# Fuente.net
KiCad netlist of a schematic drawn in Altium Designer
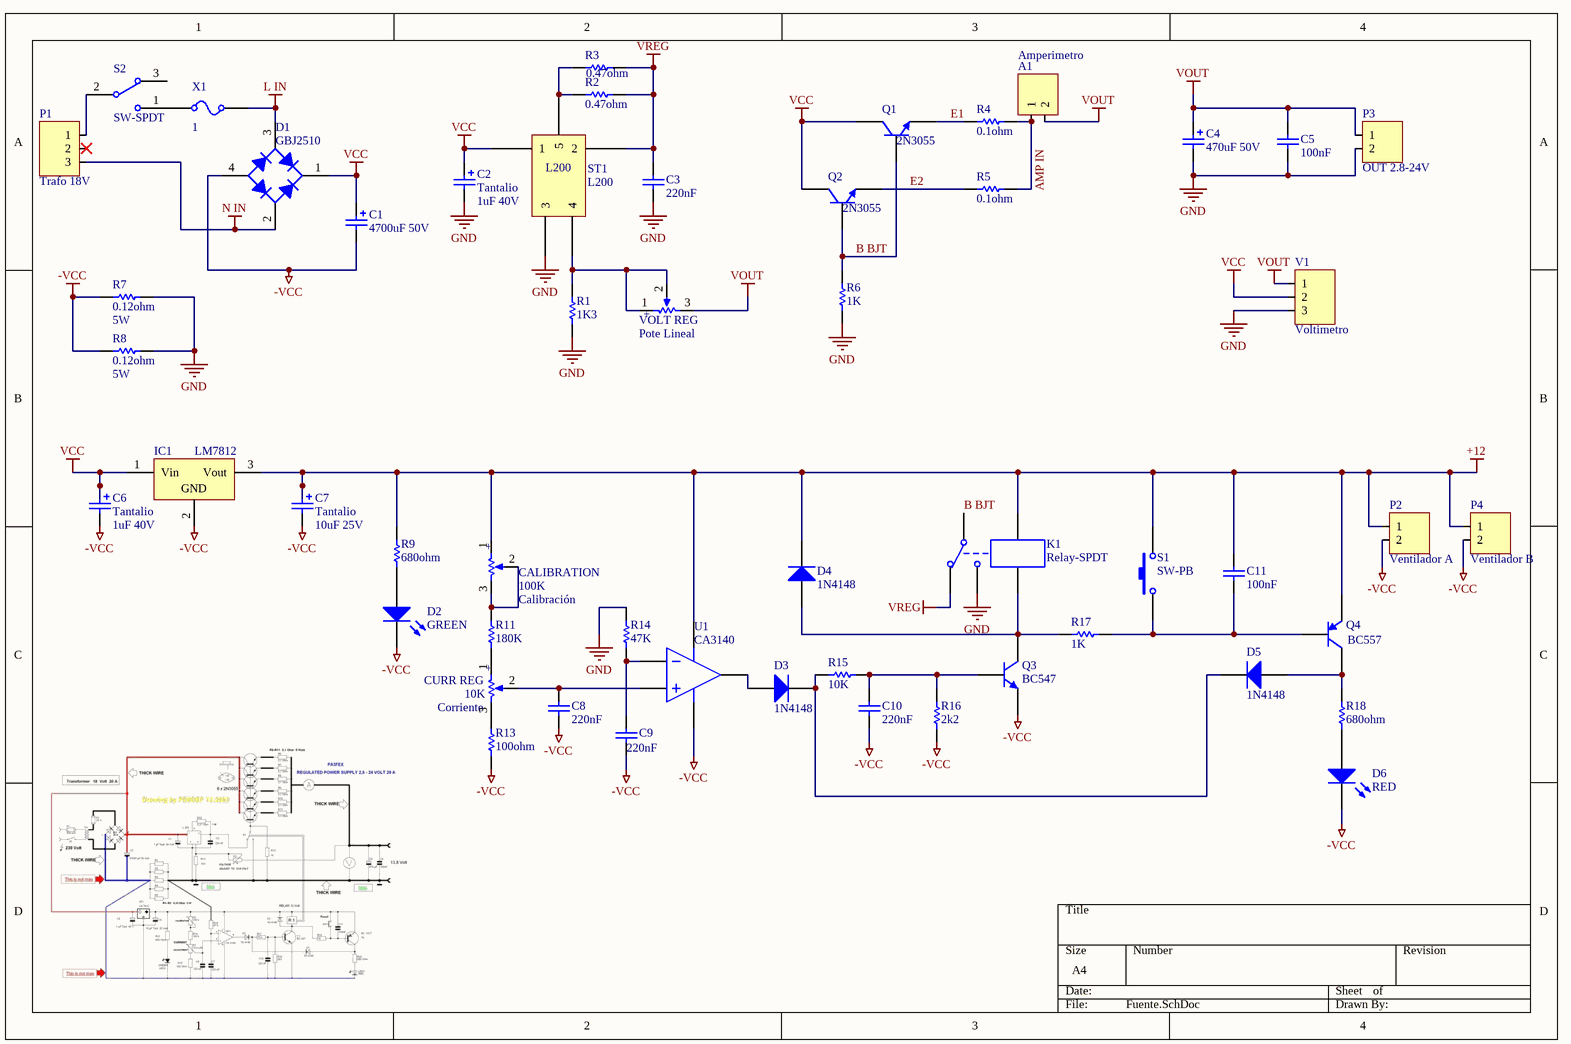
[diagram p0: Fuente.SchDoc]

(export (version "E")
  (design (tool "Eeschema 10.0.6"))
  (components
    (comp (ref "A1")
      (value "Amperimetro")
      (footprint "BORNERA 2")
      (description "Header, 2-Pin")
      (fields (field (name "PUBLISHER") "Altium Limited"))
      (libsource (lib "") (part "Bornera_1"))
    )
    (comp (ref "C1")
      (value "4700uF 50V")
      (footprint "CAP 20MM")
      (description "Polarized Capacitor (Radial)")
      (fields (field (name "PUBLISHER") "Altium Limited"))
      (libsource (lib "SchLibPutallaz") (part "Cap Pol1"))
    )
    (comp (ref "C2")
      (value "Tantalio")
      (footprint "Cap Tantalio")
      (description "Polarized Capacitor (Radial)")
      (fields (field (name "ALTIUM_VALUE") "1uF 40V") (field (name "PUBLISHER") "Altium Limited"))
      (libsource (lib "SchLibPutallaz") (part "Cap Pol1"))
    )
    (comp (ref "C3")
      (value "220nF")
      (footprint "1206 res")
      (description "Capacitor")
      (fields (field (name "PUBLISHER") "Altium Limited"))
      (libsource (lib "SchLibPutallaz") (part "Cap"))
    )
    (comp (ref "C4")
      (value "470uF 50V")
      (footprint "CAP 10mm")
      (description "Polarized Capacitor (Radial)")
      (fields (field (name "PUBLISHER") "Altium Limited"))
      (libsource (lib "SchLibPutallaz") (part "Cap Pol1"))
    )
    (comp (ref "C5")
      (value "100nF")
      (footprint "0805 res")
      (description "Capacitor")
      (fields (field (name "PUBLISHER") "Altium Limited"))
      (libsource (lib "SchLibPutallaz") (part "Cap"))
    )
    (comp (ref "C6")
      (value "Tantalio")
      (footprint "Cap Tantalio")
      (description "Polarized Capacitor (Radial)")
      (fields (field (name "ALTIUM_VALUE") "1uF 40V") (field (name "PUBLISHER") "Altium Limited"))
      (libsource (lib "SchLibPutallaz") (part "Cap Pol1"))
    )
    (comp (ref "C7")
      (value "Tantalio")
      (footprint "Cap Tantalio")
      (description "Polarized Capacitor (Radial)")
      (fields (field (name "ALTIUM_VALUE") "10uF 25V") (field (name "PUBLISHER") "Altium Limited"))
      (libsource (lib "SchLibPutallaz") (part "Cap Pol1"))
    )
    (comp (ref "C8")
      (value "220nF")
      (footprint "1206 res")
      (description "Capacitor")
      (fields (field (name "PUBLISHER") "Altium Limited"))
      (libsource (lib "SchLibPutallaz") (part "Cap"))
    )
    (comp (ref "C9")
      (value "220nF")
      (footprint "1206 res")
      (description "Capacitor")
      (fields (field (name "PUBLISHER") "Altium Limited"))
      (libsource (lib "SchLibPutallaz") (part "Cap"))
    )
    (comp (ref "C10")
      (value "220nF")
      (footprint "1206 res")
      (description "Capacitor")
      (fields (field (name "PUBLISHER") "Altium Limited"))
      (libsource (lib "SchLibPutallaz") (part "Cap"))
    )
    (comp (ref "C11")
      (value "100nF")
      (footprint "0805 res")
      (description "Capacitor")
      (fields (field (name "PUBLISHER") "Altium Limited"))
      (libsource (lib "SchLibPutallaz") (part "Cap"))
    )
    (comp (ref "CALIBRATION")
      (value "100K")
      (footprint "Potenciometro")
      (libsource (lib "SchLibPutallaz") (part "Potenciometro"))
    )
    (comp (ref "CURR REG")
      (value "10K")
      (footprint "Potenciometro")
      (libsource (lib "SchLibPutallaz") (part "Potenciometro"))
    )
    (comp (ref "D1")
      (value "GBJ2510")
      (footprint "DIOB_GBJ2510")
      (description "Full Wave Diode Bridge")
      (fields (field (name "PUBLISHER") "Altium Limited"))
      (libsource (lib "SchLibPutallaz") (part "Bridge1"))
    )
    (comp (ref "D2")
      (value "GREEN")
      (footprint "LED 5MM GREEN")
      (description "Typical BLUE SiC LED")
      (fields (field (name "PUBLISHER") "Altium Limited"))
      (libsource (lib "SchLibPutallaz") (part "LED5"))
    )
    (comp (ref "D3")
      (value "1N4148")
      (footprint "DO-38")
      (description "1 Amp General Purpose Rectifier")
      (fields (field (name "PUBLISHER") "Altium Limited"))
      (libsource (lib "SchLibPutallaz") (part "Diode 1N4007"))
    )
    (comp (ref "D4")
      (value "1N4148")
      (footprint "DO-38")
      (description "1 Amp General Purpose Rectifier")
      (fields (field (name "PUBLISHER") "Altium Limited"))
      (libsource (lib "SchLibPutallaz") (part "Diode 1N4007"))
    )
    (comp (ref "D5")
      (value "1N4148")
      (footprint "DO-38")
      (description "1 Amp General Purpose Rectifier")
      (fields (field (name "PUBLISHER") "Altium Limited"))
      (libsource (lib "SchLibPutallaz") (part "Diode 1N4007"))
    )
    (comp (ref "D6")
      (value "RED")
      (footprint "LED 5MM")
      (description "Typical BLUE SiC LED")
      (fields (field (name "PUBLISHER") "Altium Limited"))
      (libsource (lib "SchLibPutallaz") (part "LED5"))
    )
    (comp (ref "IC1") (value "LM7812") (footprint "TO220") (libsource (lib "SchLibPutallaz") (part "LM7812")))
    (comp (ref "K1")
      (value "Relay-SPDT")
      (footprint "Relay")
      (description "Single-Pole Dual-Throw Relay")
      (fields (field (name "PUBLISHER") "Altium Limited"))
      (libsource (lib "SchLibPutallaz") (part "Relay-SPDT"))
    )
    (comp (ref "P1")
      (value "Trafo 18V")
      (footprint "Bornera 3")
      (description "Header, 3-Pin")
      (fields (field (name "PUBLISHER") "Altium Limited"))
      (libsource (lib "SchLibPutallaz") (part "Bornera 3pin"))
    )
    (comp (ref "P2")
      (value "Ventilador A")
      (footprint "HDR1X2")
      (description "Header, 2-Pin")
      (fields (field (name "PUBLISHER") "Altium Limited"))
      (libsource (lib "SchLibPutallaz") (part "Header 2"))
    )
    (comp (ref "P3")
      (value "OUT 2.8-24V")
      (footprint "BORNERA 2")
      (description "Header, 2-Pin")
      (fields (field (name "PUBLISHER") "Altium Limited"))
      (libsource (lib "SchLibPutallaz") (part "Bornera"))
    )
    (comp (ref "P4")
      (value "Ventilador B")
      (footprint "HDR1X2")
      (description "Header, 2-Pin")
      (fields (field (name "PUBLISHER") "Altium Limited"))
      (libsource (lib "SchLibPutallaz") (part "Header 2"))
    )
    (comp (ref "Q1")
      (value "2N3055")
      (footprint "Bornera 3")
      (description "NPN General Purpose Amplifier")
      (fields (field (name "PUBLISHER") "Altium Limited"))
      (libsource (lib "") (part "BC547_1"))
    )
    (comp (ref "Q2")
      (value "2N3055")
      (footprint "Bornera 3")
      (description "NPN General Purpose Amplifier")
      (fields (field (name "PUBLISHER") "Altium Limited"))
      (libsource (lib "SchLibPutallaz") (part "BC547"))
    )
    (comp (ref "Q3")
      (value "BC547")
      (footprint "TO-92A")
      (description "NPN General Purpose Amplifier")
      (fields (field (name "PUBLISHER") "Altium Limited"))
      (libsource (lib "SchLibPutallaz") (part "BC547"))
    )
    (comp (ref "Q4")
      (value "BC557")
      (footprint "TO-92A")
      (description "Bipolar PNP 3 Pins Transistor Gummel-Poon Model")
      (libsource (lib "SchLibPutallaz") (part "BJT PNP GP"))
    )
    (comp (ref "R1")
      (value "1K3")
      (footprint "1206 res")
      (description "Resistor")
      (fields (field (name "PUBLISHER") "Altium Limited"))
      (libsource (lib "SchLibPutallaz") (part "Res1"))
    )
    (comp (ref "R2")
      (value "0.47ohm")
      (footprint "Res Axial 0.5")
      (description "Resistor")
      (fields (field (name "PUBLISHER") "Altium Limited"))
      (libsource (lib "SchLibPutallaz") (part "Res1"))
    )
    (comp (ref "R3")
      (value "0.47ohm")
      (footprint "Res Axial 0.5")
      (description "Resistor")
      (fields (field (name "PUBLISHER") "Altium Limited"))
      (libsource (lib "SchLibPutallaz") (part "Res1"))
    )
    (comp (ref "R4")
      (value "0.1ohm")
      (footprint "RES AXIAL 5W")
      (description "Resistor")
      (fields (field (name "PUBLISHER") "Altium Limited"))
      (libsource (lib "SchLibPutallaz") (part "Res1"))
    )
    (comp (ref "R5")
      (value "0.1ohm")
      (footprint "RES AXIAL 5W")
      (description "Resistor")
      (fields (field (name "PUBLISHER") "Altium Limited"))
      (libsource (lib "SchLibPutallaz") (part "Res1"))
    )
    (comp (ref "R6")
      (value "1K")
      (footprint "1206 res")
      (description "Resistor")
      (fields (field (name "PUBLISHER") "Altium Limited"))
      (libsource (lib "SchLibPutallaz") (part "Res1"))
    )
    (comp (ref "R7")
      (value "0.12ohm")
      (footprint "RES AXIAL 5W")
      (description "Resistor")
      (fields (field (name "ALTIUM_VALUE") "5W") (field (name "PUBLISHER") "Altium Limited"))
      (libsource (lib "SchLibPutallaz") (part "Res1"))
    )
    (comp (ref "R8")
      (value "0.12ohm")
      (footprint "RES AXIAL 5W")
      (description "Resistor")
      (fields (field (name "ALTIUM_VALUE") "5W") (field (name "PUBLISHER") "Altium Limited"))
      (libsource (lib "SchLibPutallaz") (part "Res1"))
    )
    (comp (ref "R9")
      (value "680ohm")
      (footprint "1206 res")
      (description "Resistor")
      (fields (field (name "PUBLISHER") "Altium Limited"))
      (libsource (lib "SchLibPutallaz") (part "Res1"))
    )
    (comp (ref "R11")
      (value "180K")
      (footprint "1206 res")
      (description "Resistor")
      (fields (field (name "PUBLISHER") "Altium Limited"))
      (libsource (lib "SchLibPutallaz") (part "Res1"))
    )
    (comp (ref "R13")
      (value "100ohm")
      (footprint "1206 res")
      (description "Resistor")
      (fields (field (name "PUBLISHER") "Altium Limited"))
      (libsource (lib "SchLibPutallaz") (part "Res1"))
    )
    (comp (ref "R14")
      (value "47K")
      (footprint "1206 res")
      (description "Resistor")
      (fields (field (name "PUBLISHER") "Altium Limited"))
      (libsource (lib "SchLibPutallaz") (part "Res1"))
    )
    (comp (ref "R15")
      (value "10K")
      (footprint "1206 res")
      (description "Resistor")
      (fields (field (name "PUBLISHER") "Altium Limited"))
      (libsource (lib "SchLibPutallaz") (part "Res1"))
    )
    (comp (ref "R16")
      (value "2k2")
      (footprint "1206 res")
      (description "Resistor")
      (fields (field (name "PUBLISHER") "Altium Limited"))
      (libsource (lib "SchLibPutallaz") (part "Res1"))
    )
    (comp (ref "R17")
      (value "1K")
      (footprint "1206 res")
      (description "Resistor")
      (fields (field (name "PUBLISHER") "Altium Limited"))
      (libsource (lib "SchLibPutallaz") (part "Res1"))
    )
    (comp (ref "R18")
      (value "680ohm")
      (footprint "1206 res")
      (description "Resistor")
      (fields (field (name "PUBLISHER") "Altium Limited"))
      (libsource (lib "SchLibPutallaz") (part "Res1"))
    )
    (comp (ref "S1")
      (value "SW-PB")
      (footprint "Pulsador")
      (description "Switch")
      (fields (field (name "PUBLISHER") "Altium Limited"))
      (libsource (lib "SchLibPutallaz") (part "SW-PNA"))
    )
    (comp (ref "S2")
      (value "SW-SPDT")
      (footprint "Bornera 3")
      (description "SPDT Subminiature Toggle Switch, Right Angle Mounting, Vertical Actuation")
      (fields (field (name "PUBLISHER") "Altium Limited"))
      (libsource (lib "SchLibPutallaz") (part "SW-SPDT"))
    )
    (comp (ref "ST1") (value "L200") (footprint "PENTAWATT") (libsource (lib "Fuente") (part "L200")))
    (comp (ref "U1")
      (value "Amplificador Operacional")
      (footprint "DIP8")
      (description "Ideal Operational Amplifier")
      (libsource (lib "SchLibPutallaz") (part "OpAmp with power terminals"))
    )
    (comp (ref "V1")
      (value "Voltimetro")
      (footprint "HDR1X3")
      (description "Header, 3-Pin")
      (fields (field (name "PUBLISHER") "Altium Limited"))
      (libsource (lib "SchLibPutallaz") (part "Header 3"))
    )
    (comp (ref "VOLT REG")
      (value "Pote Lineal")
      (footprint "Potenciometro")
      (libsource (lib "SchLibPutallaz") (part "Potenciometro"))
    )
    (comp (ref "X1")
      (value "Fuse")
      (footprint "Fusiblera")
      (fields (field (name "CURRENT") "1"))
      (libsource (lib "Fuente") (part "Fuse_1"))
    )
  )
  (nets
    (net (code "1") (name "+12") (class "Default")
      (node (ref "C11") (pin "2") (pinfunction "2_2") (pintype "passive"))
      (node (ref "C7") (pin "1") (pinfunction "1_1") (pintype "passive"))
      (node (ref "CALIBRATION") (pin "1") (pinfunction "TOP_1") (pintype "passive"))
      (node (ref "D4") (pin "2") (pinfunction "K_2") (pintype "passive"))
      (node (ref "IC1") (pin "3") (pinfunction "Vout_3") (pintype "passive"))
      (node (ref "K1") (pin "1") (pinfunction "1_1") (pintype "passive"))
      (node (ref "P2") (pin "1") (pinfunction "1_1") (pintype "passive"))
      (node (ref "P4") (pin "1") (pinfunction "1_1") (pintype "passive"))
      (node (ref "Q4") (pin "3") (pinfunction "E_3") (pintype "passive"))
      (node (ref "R9") (pin "2") (pinfunction "2_2") (pintype "passive"))
      (node (ref "S1") (pin "2") (pinfunction "2_2") (pintype "passive"))
      (node (ref "U1") (pin "7") (pinfunction "V+_7") (pintype "power_in"))
    )
    (net (code "2") (name "-VCC") (class "Default")
      (node (ref "C1") (pin "2") (pinfunction "2_2") (pintype "passive"))
      (node (ref "C10") (pin "1") (pinfunction "1_1") (pintype "passive"))
      (node (ref "C6") (pin "2") (pinfunction "2_2") (pintype "passive"))
      (node (ref "C7") (pin "2") (pinfunction "2_2") (pintype "passive"))
      (node (ref "C8") (pin "1") (pinfunction "1_1") (pintype "passive"))
      (node (ref "C9") (pin "1") (pinfunction "1_1") (pintype "passive"))
      (node (ref "D1") (pin "4") (pinfunction "A_4") (pintype "passive"))
      (node (ref "D2") (pin "2") (pinfunction "K_2") (pintype "passive"))
      (node (ref "D6") (pin "2") (pinfunction "K_2") (pintype "passive"))
      (node (ref "IC1") (pin "2") (pinfunction "GND_2") (pintype "passive"))
      (node (ref "P2") (pin "2") (pinfunction "2_2") (pintype "passive"))
      (node (ref "P4") (pin "2") (pinfunction "2_2") (pintype "passive"))
      (node (ref "Q3") (pin "3") (pinfunction "E_3") (pintype "passive"))
      (node (ref "R13") (pin "1") (pinfunction "1_1") (pintype "passive"))
      (node (ref "R16") (pin "1") (pinfunction "1_1") (pintype "passive"))
      (node (ref "R7") (pin "1") (pinfunction "1_1") (pintype "passive"))
      (node (ref "R8") (pin "1") (pinfunction "1_1") (pintype "passive"))
      (node (ref "U1") (pin "4") (pinfunction "V-_4") (pintype "power_in"))
    )
    (net (code "3") (name "/AMP IN") (class "Default")
      (node (ref "A1") (pin "1") (pinfunction "1_1") (pintype "passive"))
      (node (ref "R4") (pin "2") (pinfunction "2_2") (pintype "passive"))
      (node (ref "R5") (pin "2") (pinfunction "2_2") (pintype "passive"))
    )
    (net (code "4") (name "/B BJT") (class "Default")
      (node (ref "K1") (pin "3") (pinfunction "3_3") (pintype "passive"))
      (node (ref "Q1") (pin "2") (pinfunction "B_2") (pintype "passive"))
      (node (ref "Q2") (pin "2") (pinfunction "B_2") (pintype "passive"))
      (node (ref "R6") (pin "2") (pinfunction "2_2") (pintype "passive"))
    )
    (net (code "5") (name "/E1") (class "Default")
      (node (ref "Q1") (pin "1") (pinfunction "E_1") (pintype "passive"))
      (node (ref "R4") (pin "1") (pinfunction "1_1") (pintype "passive"))
    )
    (net (code "6") (name "/E2") (class "Default")
      (node (ref "Q2") (pin "3") (pinfunction "E_3") (pintype "passive"))
      (node (ref "R5") (pin "1") (pinfunction "1_1") (pintype "passive"))
    )
    (net (code "7") (name "GND") (class "Default")
      (node (ref "C2") (pin "2") (pinfunction "2_2") (pintype "passive"))
      (node (ref "C3") (pin "1") (pinfunction "1_1") (pintype "passive"))
      (node (ref "C4") (pin "2") (pinfunction "2_2") (pintype "passive"))
      (node (ref "C5") (pin "1") (pinfunction "1_1") (pintype "passive"))
      (node (ref "K1") (pin "5") (pinfunction "5_5") (pintype "passive"))
      (node (ref "P3") (pin "1") (pinfunction "2_1") (pintype "passive"))
      (node (ref "R1") (pin "1") (pinfunction "1_1") (pintype "passive"))
      (node (ref "R14") (pin "2") (pinfunction "2_2") (pintype "passive"))
      (node (ref "R6") (pin "1") (pinfunction "1_1") (pintype "passive"))
      (node (ref "R7") (pin "2") (pinfunction "2_2") (pintype "passive"))
      (node (ref "R8") (pin "2") (pinfunction "2_2") (pintype "passive"))
      (node (ref "ST1") (pin "3") (pinfunction "3_3") (pintype "passive"))
      (node (ref "V1") (pin "3") (pinfunction "3_3") (pintype "passive"))
    )
    (net (code "8") (name "L IN") (class "Default")
      (node (ref "D1") (pin "3") (pinfunction "C_3") (pintype "passive"))
      (node (ref "X1") (pin "2") (pinfunction "2_2") (pintype "passive"))
    )
    (net (code "9") (name "N IN") (class "Default")
      (node (ref "D1") (pin "2") (pinfunction "C_2") (pintype "passive"))
      (node (ref "P1") (pin "3") (pinfunction "3_3") (pintype "passive"))
    )
    (net (code "10") (name "Net-(CALIBRATION-BOTTOM)") (class "Default")
      (node (ref "CALIBRATION") (pin "2") (pinfunction "TAP_2") (pintype "passive"))
      (node (ref "CALIBRATION") (pin "3") (pinfunction "BOTTOM_3") (pintype "passive"))
      (node (ref "R11") (pin "2") (pinfunction "2_2") (pintype "passive"))
    )
    (net (code "11") (name "Net-(CURR REG-BOTTOM)") (class "Default")
      (node (ref "CURR REG") (pin "3") (pinfunction "BOTTOM_3") (pintype "passive"))
      (node (ref "R13") (pin "2") (pinfunction "2_2") (pintype "passive"))
    )
    (net (code "12") (name "Net-(CURR REG-TAP)") (class "Default")
      (node (ref "C8") (pin "2") (pinfunction "2_2") (pintype "passive"))
      (node (ref "CURR REG") (pin "2") (pinfunction "TAP_2") (pintype "passive"))
      (node (ref "U1") (pin "3") (pinfunction "IN+_3") (pintype "passive"))
    )
    (net (code "13") (name "Net-(CURR REG-TOP)") (class "Default")
      (node (ref "CURR REG") (pin "1") (pinfunction "TOP_1") (pintype "passive"))
      (node (ref "R11") (pin "1") (pinfunction "1_1") (pintype "passive"))
    )
    (net (code "14") (name "Net-(D2-A)") (class "Default")
      (node (ref "D2") (pin "1") (pinfunction "A_1") (pintype "passive"))
      (node (ref "R9") (pin "1") (pinfunction "1_1") (pintype "passive"))
    )
    (net (code "15") (name "Net-(D3-A)") (class "Default")
      (node (ref "D3") (pin "1") (pinfunction "A_1") (pintype "passive"))
      (node (ref "U1") (pin "6") (pinfunction "OUT_6") (pintype "passive"))
    )
    (net (code "16") (name "Net-(D3-K)") (class "Default")
      (node (ref "D3") (pin "2") (pinfunction "K_2") (pintype "passive"))
      (node (ref "D5") (pin "2") (pinfunction "K_2") (pintype "passive"))
      (node (ref "R15") (pin "1") (pinfunction "1_1") (pintype "passive"))
    )
    (net (code "17") (name "Net-(D4-A)") (class "Default")
      (node (ref "D4") (pin "1") (pinfunction "A_1") (pintype "passive"))
      (node (ref "K1") (pin "2") (pinfunction "2_2") (pintype "passive"))
      (node (ref "Q3") (pin "1") (pinfunction "C_1") (pintype "passive"))
      (node (ref "R17") (pin "1") (pinfunction "1_1") (pintype "passive"))
    )
    (net (code "18") (name "Net-(D5-A)") (class "Default")
      (node (ref "D5") (pin "1") (pinfunction "A_1") (pintype "passive"))
      (node (ref "Q4") (pin "1") (pinfunction "C_1") (pintype "passive"))
      (node (ref "R18") (pin "2") (pinfunction "2_2") (pintype "passive"))
    )
    (net (code "19") (name "Net-(D6-A)") (class "Default")
      (node (ref "D6") (pin "1") (pinfunction "A_1") (pintype "passive"))
      (node (ref "R18") (pin "1") (pinfunction "1_1") (pintype "passive"))
    )
    (net (code "20") (name "Net-(Q3-B)") (class "Default")
      (node (ref "C10") (pin "2") (pinfunction "2_2") (pintype "passive"))
      (node (ref "Q3") (pin "2") (pinfunction "B_2") (pintype "passive"))
      (node (ref "R15") (pin "2") (pinfunction "2_2") (pintype "passive"))
      (node (ref "R16") (pin "2") (pinfunction "2_2") (pintype "passive"))
    )
    (net (code "21") (name "Net-(Q4-B)") (class "Default")
      (node (ref "C11") (pin "1") (pinfunction "1_1") (pintype "passive"))
      (node (ref "Q4") (pin "2") (pinfunction "B_2") (pintype "passive"))
      (node (ref "R17") (pin "2") (pinfunction "2_2") (pintype "passive"))
      (node (ref "S1") (pin "1") (pinfunction "1_1") (pintype "passive"))
    )
    (net (code "22") (name "Net-(R2-Pad1)") (class "Default")
      (node (ref "R2") (pin "1") (pinfunction "1_1") (pintype "passive"))
      (node (ref "R3") (pin "1") (pinfunction "1_1") (pintype "passive"))
      (node (ref "ST1") (pin "5") (pinfunction "5_5") (pintype "passive"))
    )
    (net (code "23") (name "Net-(S2-1)") (class "Default")
      (node (ref "P1") (pin "1") (pinfunction "1_1") (pintype "passive"))
      (node (ref "S2") (pin "2") (pinfunction "1_2") (pintype "passive"))
    )
    (net (code "24") (name "Net-(S2-2)") (class "Default")
      (node (ref "S2") (pin "1") (pinfunction "2_1") (pintype "passive"))
      (node (ref "X1") (pin "1") (pinfunction "1_1") (pintype "passive"))
    )
    (net (code "25") (name "Net-(U1-IN-)") (class "Default")
      (node (ref "C9") (pin "2") (pinfunction "2_2") (pintype "passive"))
      (node (ref "R14") (pin "1") (pinfunction "1_1") (pintype "passive"))
      (node (ref "U1") (pin "2") (pinfunction "IN-_2") (pintype "passive"))
    )
    (net (code "26") (name "Net-(VOLT REG-TAP)") (class "Default")
      (node (ref "R1") (pin "2") (pinfunction "2_2") (pintype "passive"))
      (node (ref "ST1") (pin "4") (pinfunction "4_4") (pintype "passive"))
      (node (ref "VOLT REG") (pin "1") (pinfunction "TOP_1") (pintype "passive"))
      (node (ref "VOLT REG") (pin "2") (pinfunction "TAP_2") (pintype "passive"))
    )
    (net (code "27") (name "VCC") (class "Default")
      (node (ref "C1") (pin "1") (pinfunction "1_1") (pintype "passive"))
      (node (ref "C2") (pin "1") (pinfunction "1_1") (pintype "passive"))
      (node (ref "C6") (pin "1") (pinfunction "1_1") (pintype "passive"))
      (node (ref "D1") (pin "1") (pinfunction "K_1") (pintype "passive"))
      (node (ref "IC1") (pin "1") (pinfunction "Vin_1") (pintype "passive"))
      (node (ref "Q1") (pin "3") (pinfunction "C_3") (pintype "passive"))
      (node (ref "Q2") (pin "1") (pinfunction "C_1") (pintype "passive"))
      (node (ref "ST1") (pin "1") (pinfunction "1_1") (pintype "passive"))
      (node (ref "V1") (pin "2") (pinfunction "2_2") (pintype "passive"))
    )
    (net (code "28") (name "VOUT") (class "Default")
      (node (ref "A1") (pin "2") (pinfunction "2_2") (pintype "passive"))
      (node (ref "C4") (pin "1") (pinfunction "1_1") (pintype "passive"))
      (node (ref "C5") (pin "2") (pinfunction "2_2") (pintype "passive"))
      (node (ref "P3") (pin "2") (pinfunction "1_2") (pintype "passive"))
      (node (ref "V1") (pin "1") (pinfunction "1_1") (pintype "passive"))
      (node (ref "VOLT REG") (pin "3") (pinfunction "BOTTOM_3") (pintype "passive"))
    )
    (net (code "29") (name "VREG") (class "Default")
      (node (ref "C3") (pin "2") (pinfunction "2_2") (pintype "passive"))
      (node (ref "K1") (pin "4") (pinfunction "4_4") (pintype "passive"))
      (node (ref "R2") (pin "2") (pinfunction "2_2") (pintype "passive"))
      (node (ref "R3") (pin "2") (pinfunction "2_2") (pintype "passive"))
      (node (ref "ST1") (pin "2") (pinfunction "2_2") (pintype "passive"))
    )
    (net (code "30") (name "unconnected-(P1-Pad2)") (class "Default")
      (node (ref "P1") (pin "2") (pinfunction "2_2") (pintype "passive+no_connect"))
    )
    (net (code "31") (name "unconnected-(S2-Pad3)") (class "Default")
      (node (ref "S2") (pin "3") (pinfunction "3_3") (pintype "passive"))
    )
  )
)
